# Relays.net
KiCad netlist of a schematic drawn in Altium Designer
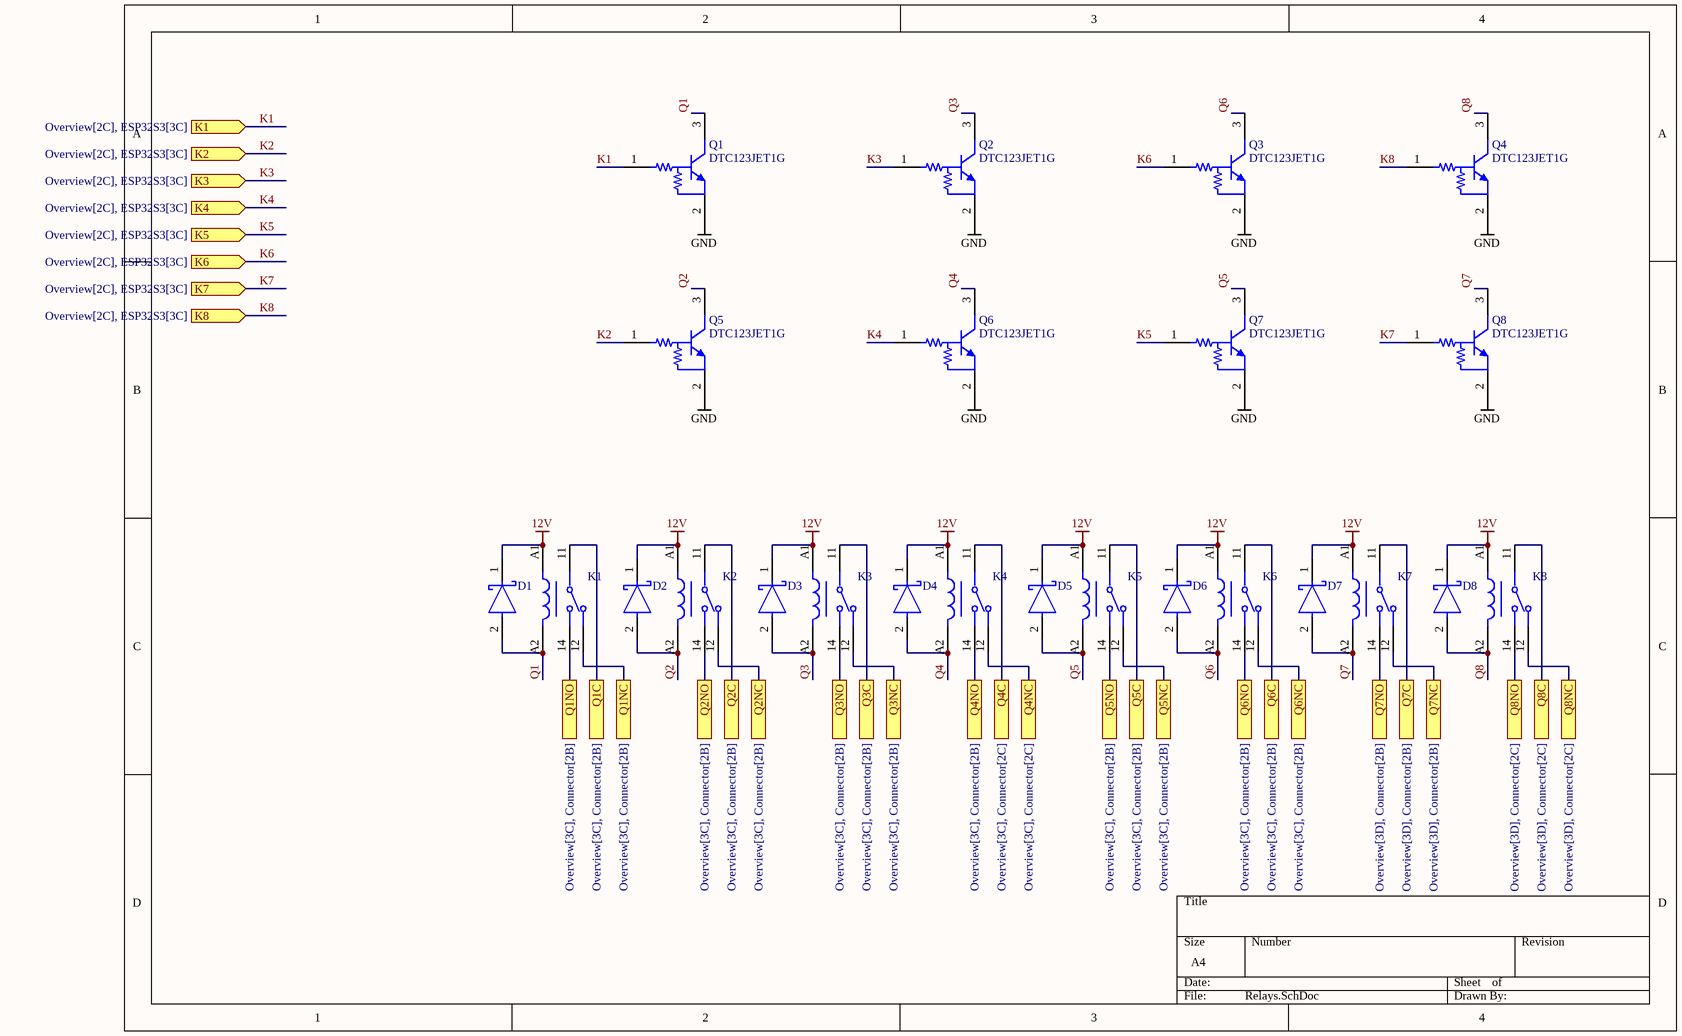
[diagram p0: Relays.SchDoc]

(export (version "E")
  (design (tool "Eeschema 10.0.6"))
  (components
    (comp (ref "D1")
      (value "SBR80520LT1G")
      (footprint "FP-425-04-MFG")
      (description "DIODE SCHOTTKY 20V 500MA SOD123")
      (libsource (lib "Altium Content Vault") (part "1d6ec82d83fb6aee721767c19dac4b9"))
    )
    (comp (ref "D2")
      (value "SBR80520LT1G")
      (footprint "FP-425-04-MFG")
      (description "DIODE SCHOTTKY 20V 500MA SOD123")
      (libsource (lib "Altium Content Vault") (part "1d6ec82d83fb6aee721767c19dac4b9"))
    )
    (comp (ref "D3")
      (value "SBR80520LT1G")
      (footprint "FP-425-04-MFG")
      (description "DIODE SCHOTTKY 20V 500MA SOD123")
      (libsource (lib "Altium Content Vault") (part "1d6ec82d83fb6aee721767c19dac4b9"))
    )
    (comp (ref "D4")
      (value "SBR80520LT1G")
      (footprint "FP-425-04-MFG")
      (description "DIODE SCHOTTKY 20V 500MA SOD123")
      (libsource (lib "Altium Content Vault") (part "1d6ec82d83fb6aee721767c19dac4b9"))
    )
    (comp (ref "D5")
      (value "SBR80520LT1G")
      (footprint "FP-425-04-MFG")
      (description "DIODE SCHOTTKY 20V 500MA SOD123")
      (libsource (lib "Altium Content Vault") (part "1d6ec82d83fb6aee721767c19dac4b9"))
    )
    (comp (ref "D6")
      (value "SBR80520LT1G")
      (footprint "FP-425-04-MFG")
      (description "DIODE SCHOTTKY 20V 500MA SOD123")
      (libsource (lib "Altium Content Vault") (part "1d6ec82d83fb6aee721767c19dac4b9"))
    )
    (comp (ref "D7")
      (value "SBR80520LT1G")
      (footprint "FP-425-04-MFG")
      (description "DIODE SCHOTTKY 20V 500MA SOD123")
      (libsource (lib "Altium Content Vault") (part "1d6ec82d83fb6aee721767c19dac4b9"))
    )
    (comp (ref "D8")
      (value "SBR80520LT1G")
      (footprint "FP-425-04-MFG")
      (description "DIODE SCHOTTKY 20V 500MA SOD123")
      (libsource (lib "Altium Content Vault") (part "1d6ec82d83fb6aee721767c19dac4b9"))
    )
    (comp (ref "K1")
      (value "7-1415899-7")
      (footprint "FP-7-1415899-7-MFG")
      (description "RELAY GEN PURPOSE SPDT 16A 12V")
      (libsource (lib "Altium Content Vault") (part "5616896f2940a2f659fdf8b644a2cf0"))
    )
    (comp (ref "K2")
      (value "7-1415899-7")
      (footprint "FP-7-1415899-7-MFG")
      (description "RELAY GEN PURPOSE SPDT 16A 12V")
      (libsource (lib "Altium Content Vault") (part "5616896f2940a2f659fdf8b644a2cf0"))
    )
    (comp (ref "K3")
      (value "7-1415899-7")
      (footprint "FP-7-1415899-7-MFG")
      (description "RELAY GEN PURPOSE SPDT 16A 12V")
      (libsource (lib "Altium Content Vault") (part "5616896f2940a2f659fdf8b644a2cf0"))
    )
    (comp (ref "K4")
      (value "7-1415899-7")
      (footprint "FP-7-1415899-7-MFG")
      (description "RELAY GEN PURPOSE SPDT 16A 12V")
      (libsource (lib "Altium Content Vault") (part "5616896f2940a2f659fdf8b644a2cf0"))
    )
    (comp (ref "K5")
      (value "7-1415899-7")
      (footprint "FP-7-1415899-7-MFG")
      (description "RELAY GEN PURPOSE SPDT 16A 12V")
      (libsource (lib "Altium Content Vault") (part "5616896f2940a2f659fdf8b644a2cf0"))
    )
    (comp (ref "K6")
      (value "7-1415899-7")
      (footprint "FP-7-1415899-7-MFG")
      (description "RELAY GEN PURPOSE SPDT 16A 12V")
      (libsource (lib "Altium Content Vault") (part "5616896f2940a2f659fdf8b644a2cf0"))
    )
    (comp (ref "K7")
      (value "7-1415899-7")
      (footprint "FP-7-1415899-7-MFG")
      (description "RELAY GEN PURPOSE SPDT 16A 12V")
      (libsource (lib "Altium Content Vault") (part "5616896f2940a2f659fdf8b644a2cf0"))
    )
    (comp (ref "K8")
      (value "7-1415899-7")
      (footprint "FP-7-1415899-7-MFG")
      (description "RELAY GEN PURPOSE SPDT 16A 12V")
      (libsource (lib "Altium Content Vault") (part "5616896f2940a2f659fdf8b644a2cf0"))
    )
    (comp (ref "Q1")
      (value "DTC123JET1G")
      (footprint "ONSC-SC-75-3-463-01_V")
      (fields (field (name "MANUFACTURER") "On Semiconductor"))
      (libsource (lib "Altium Content Vault") (part "ONSC-BRT-NPN-B1E2C3-3"))
    )
    (comp (ref "Q2")
      (value "DTC123JET1G")
      (footprint "ONSC-SC-75-3-463-01_V")
      (fields (field (name "MANUFACTURER") "On Semiconductor"))
      (libsource (lib "Altium Content Vault") (part "ONSC-BRT-NPN-B1E2C3-3"))
    )
    (comp (ref "Q3")
      (value "DTC123JET1G")
      (footprint "ONSC-SC-75-3-463-01_V")
      (fields (field (name "MANUFACTURER") "On Semiconductor"))
      (libsource (lib "Altium Content Vault") (part "ONSC-BRT-NPN-B1E2C3-3"))
    )
    (comp (ref "Q4")
      (value "DTC123JET1G")
      (footprint "ONSC-SC-75-3-463-01_V")
      (fields (field (name "MANUFACTURER") "On Semiconductor"))
      (libsource (lib "Altium Content Vault") (part "ONSC-BRT-NPN-B1E2C3-3"))
    )
    (comp (ref "Q5")
      (value "DTC123JET1G")
      (footprint "ONSC-SC-75-3-463-01_V")
      (fields (field (name "MANUFACTURER") "On Semiconductor"))
      (libsource (lib "Altium Content Vault") (part "ONSC-BRT-NPN-B1E2C3-3"))
    )
    (comp (ref "Q6")
      (value "DTC123JET1G")
      (footprint "ONSC-SC-75-3-463-01_V")
      (fields (field (name "MANUFACTURER") "On Semiconductor"))
      (libsource (lib "Altium Content Vault") (part "ONSC-BRT-NPN-B1E2C3-3"))
    )
    (comp (ref "Q7")
      (value "DTC123JET1G")
      (footprint "ONSC-SC-75-3-463-01_V")
      (fields (field (name "MANUFACTURER") "On Semiconductor"))
      (libsource (lib "Altium Content Vault") (part "ONSC-BRT-NPN-B1E2C3-3"))
    )
    (comp (ref "Q8")
      (value "DTC123JET1G")
      (footprint "ONSC-SC-75-3-463-01_V")
      (fields (field (name "MANUFACTURER") "On Semiconductor"))
      (libsource (lib "Altium Content Vault") (part "ONSC-BRT-NPN-B1E2C3-3"))
    )
  )
  (nets
    (net (code "1") (name "/K1") (class "Default")
      (node (ref "Q1") (pin "1") (pinfunction "B_1") (pintype "passive"))
    )
    (net (code "2") (name "/K2") (class "Default")
      (node (ref "Q5") (pin "1") (pinfunction "B_1") (pintype "passive"))
    )
    (net (code "3") (name "/K3") (class "Default")
      (node (ref "Q2") (pin "1") (pinfunction "B_1") (pintype "passive"))
    )
    (net (code "4") (name "/K4") (class "Default")
      (node (ref "Q6") (pin "1") (pinfunction "B_1") (pintype "passive"))
    )
    (net (code "5") (name "/K5") (class "Default")
      (node (ref "Q7") (pin "1") (pinfunction "B_1") (pintype "passive"))
    )
    (net (code "6") (name "/K6") (class "Default")
      (node (ref "Q3") (pin "1") (pinfunction "B_1") (pintype "passive"))
    )
    (net (code "7") (name "/K7") (class "Default")
      (node (ref "Q8") (pin "1") (pinfunction "B_1") (pintype "passive"))
    )
    (net (code "8") (name "/K8") (class "Default")
      (node (ref "Q4") (pin "1") (pinfunction "B_1") (pintype "passive"))
    )
    (net (code "9") (name "/Q1") (class "Default")
      (node (ref "D1") (pin "2") (pinfunction "A_2") (pintype "passive"))
      (node (ref "K1") (pin "A2") (pinfunction "A2_A2") (pintype "passive"))
      (node (ref "Q1") (pin "3") (pinfunction "C_3") (pintype "passive"))
    )
    (net (code "10") (name "/Q1C") (class "Default")
      (node (ref "K1") (pin "11") (pinfunction "11_11") (pintype "passive"))
    )
    (net (code "11") (name "/Q1NC") (class "Default")
      (node (ref "K1") (pin "12") (pinfunction "12_12") (pintype "passive"))
    )
    (net (code "12") (name "/Q1NO") (class "Default")
      (node (ref "K1") (pin "14") (pinfunction "14_14") (pintype "passive"))
    )
    (net (code "13") (name "/Q2") (class "Default")
      (node (ref "D2") (pin "2") (pinfunction "A_2") (pintype "passive"))
      (node (ref "K2") (pin "A2") (pinfunction "A2_A2") (pintype "passive"))
      (node (ref "Q5") (pin "3") (pinfunction "C_3") (pintype "passive"))
    )
    (net (code "14") (name "/Q2C") (class "Default")
      (node (ref "K2") (pin "11") (pinfunction "11_11") (pintype "passive"))
    )
    (net (code "15") (name "/Q2NC") (class "Default")
      (node (ref "K2") (pin "12") (pinfunction "12_12") (pintype "passive"))
    )
    (net (code "16") (name "/Q2NO") (class "Default")
      (node (ref "K2") (pin "14") (pinfunction "14_14") (pintype "passive"))
    )
    (net (code "17") (name "/Q3") (class "Default")
      (node (ref "D3") (pin "2") (pinfunction "A_2") (pintype "passive"))
      (node (ref "K3") (pin "A2") (pinfunction "A2_A2") (pintype "passive"))
      (node (ref "Q2") (pin "3") (pinfunction "C_3") (pintype "passive"))
    )
    (net (code "18") (name "/Q3C") (class "Default")
      (node (ref "K3") (pin "11") (pinfunction "11_11") (pintype "passive"))
    )
    (net (code "19") (name "/Q3NC") (class "Default")
      (node (ref "K3") (pin "12") (pinfunction "12_12") (pintype "passive"))
    )
    (net (code "20") (name "/Q3NO") (class "Default")
      (node (ref "K3") (pin "14") (pinfunction "14_14") (pintype "passive"))
    )
    (net (code "21") (name "/Q4") (class "Default")
      (node (ref "D4") (pin "2") (pinfunction "A_2") (pintype "passive"))
      (node (ref "K4") (pin "A2") (pinfunction "A2_A2") (pintype "passive"))
      (node (ref "Q6") (pin "3") (pinfunction "C_3") (pintype "passive"))
    )
    (net (code "22") (name "/Q4C") (class "Default")
      (node (ref "K4") (pin "11") (pinfunction "11_11") (pintype "passive"))
    )
    (net (code "23") (name "/Q4NC") (class "Default")
      (node (ref "K4") (pin "12") (pinfunction "12_12") (pintype "passive"))
    )
    (net (code "24") (name "/Q4NO") (class "Default")
      (node (ref "K4") (pin "14") (pinfunction "14_14") (pintype "passive"))
    )
    (net (code "25") (name "/Q5") (class "Default")
      (node (ref "D5") (pin "2") (pinfunction "A_2") (pintype "passive"))
      (node (ref "K5") (pin "A2") (pinfunction "A2_A2") (pintype "passive"))
      (node (ref "Q7") (pin "3") (pinfunction "C_3") (pintype "passive"))
    )
    (net (code "26") (name "/Q5C") (class "Default")
      (node (ref "K5") (pin "11") (pinfunction "11_11") (pintype "passive"))
    )
    (net (code "27") (name "/Q5NC") (class "Default")
      (node (ref "K5") (pin "12") (pinfunction "12_12") (pintype "passive"))
    )
    (net (code "28") (name "/Q5NO") (class "Default")
      (node (ref "K5") (pin "14") (pinfunction "14_14") (pintype "passive"))
    )
    (net (code "29") (name "/Q6") (class "Default")
      (node (ref "D6") (pin "2") (pinfunction "A_2") (pintype "passive"))
      (node (ref "K6") (pin "A2") (pinfunction "A2_A2") (pintype "passive"))
      (node (ref "Q3") (pin "3") (pinfunction "C_3") (pintype "passive"))
    )
    (net (code "30") (name "/Q6C") (class "Default")
      (node (ref "K6") (pin "11") (pinfunction "11_11") (pintype "passive"))
    )
    (net (code "31") (name "/Q6NC") (class "Default")
      (node (ref "K6") (pin "12") (pinfunction "12_12") (pintype "passive"))
    )
    (net (code "32") (name "/Q6NO") (class "Default")
      (node (ref "K6") (pin "14") (pinfunction "14_14") (pintype "passive"))
    )
    (net (code "33") (name "/Q7") (class "Default")
      (node (ref "D7") (pin "2") (pinfunction "A_2") (pintype "passive"))
      (node (ref "K7") (pin "A2") (pinfunction "A2_A2") (pintype "passive"))
      (node (ref "Q8") (pin "3") (pinfunction "C_3") (pintype "passive"))
    )
    (net (code "34") (name "/Q7C") (class "Default")
      (node (ref "K7") (pin "11") (pinfunction "11_11") (pintype "passive"))
    )
    (net (code "35") (name "/Q7NC") (class "Default")
      (node (ref "K7") (pin "12") (pinfunction "12_12") (pintype "passive"))
    )
    (net (code "36") (name "/Q7NO") (class "Default")
      (node (ref "K7") (pin "14") (pinfunction "14_14") (pintype "passive"))
    )
    (net (code "37") (name "/Q8") (class "Default")
      (node (ref "D8") (pin "2") (pinfunction "A_2") (pintype "passive"))
      (node (ref "K8") (pin "A2") (pinfunction "A2_A2") (pintype "passive"))
      (node (ref "Q4") (pin "3") (pinfunction "C_3") (pintype "passive"))
    )
    (net (code "38") (name "/Q8C") (class "Default")
      (node (ref "K8") (pin "11") (pinfunction "11_11") (pintype "passive"))
    )
    (net (code "39") (name "/Q8NC") (class "Default")
      (node (ref "K8") (pin "12") (pinfunction "12_12") (pintype "passive"))
    )
    (net (code "40") (name "/Q8NO") (class "Default")
      (node (ref "K8") (pin "14") (pinfunction "14_14") (pintype "passive"))
    )
    (net (code "41") (name "12V") (class "Default")
      (node (ref "D1") (pin "1") (pinfunction "C_1") (pintype "passive"))
      (node (ref "D2") (pin "1") (pinfunction "C_1") (pintype "passive"))
      (node (ref "D3") (pin "1") (pinfunction "C_1") (pintype "passive"))
      (node (ref "D4") (pin "1") (pinfunction "C_1") (pintype "passive"))
      (node (ref "D5") (pin "1") (pinfunction "C_1") (pintype "passive"))
      (node (ref "D6") (pin "1") (pinfunction "C_1") (pintype "passive"))
      (node (ref "D7") (pin "1") (pinfunction "C_1") (pintype "passive"))
      (node (ref "D8") (pin "1") (pinfunction "C_1") (pintype "passive"))
      (node (ref "K1") (pin "A1") (pinfunction "A1_A1") (pintype "passive"))
      (node (ref "K2") (pin "A1") (pinfunction "A1_A1") (pintype "passive"))
      (node (ref "K3") (pin "A1") (pinfunction "A1_A1") (pintype "passive"))
      (node (ref "K4") (pin "A1") (pinfunction "A1_A1") (pintype "passive"))
      (node (ref "K5") (pin "A1") (pinfunction "A1_A1") (pintype "passive"))
      (node (ref "K6") (pin "A1") (pinfunction "A1_A1") (pintype "passive"))
      (node (ref "K7") (pin "A1") (pinfunction "A1_A1") (pintype "passive"))
      (node (ref "K8") (pin "A1") (pinfunction "A1_A1") (pintype "passive"))
    )
    (net (code "42") (name "GND") (class "Default")
      (node (ref "Q1") (pin "2") (pinfunction "E_2") (pintype "passive"))
      (node (ref "Q2") (pin "2") (pinfunction "E_2") (pintype "passive"))
      (node (ref "Q3") (pin "2") (pinfunction "E_2") (pintype "passive"))
      (node (ref "Q4") (pin "2") (pinfunction "E_2") (pintype "passive"))
      (node (ref "Q5") (pin "2") (pinfunction "E_2") (pintype "passive"))
      (node (ref "Q6") (pin "2") (pinfunction "E_2") (pintype "passive"))
      (node (ref "Q7") (pin "2") (pinfunction "E_2") (pintype "passive"))
      (node (ref "Q8") (pin "2") (pinfunction "E_2") (pintype "passive"))
    )
  )
)
